# SCHEMATIC.net
KiCad netlist of a schematic drawn in EasyEDA
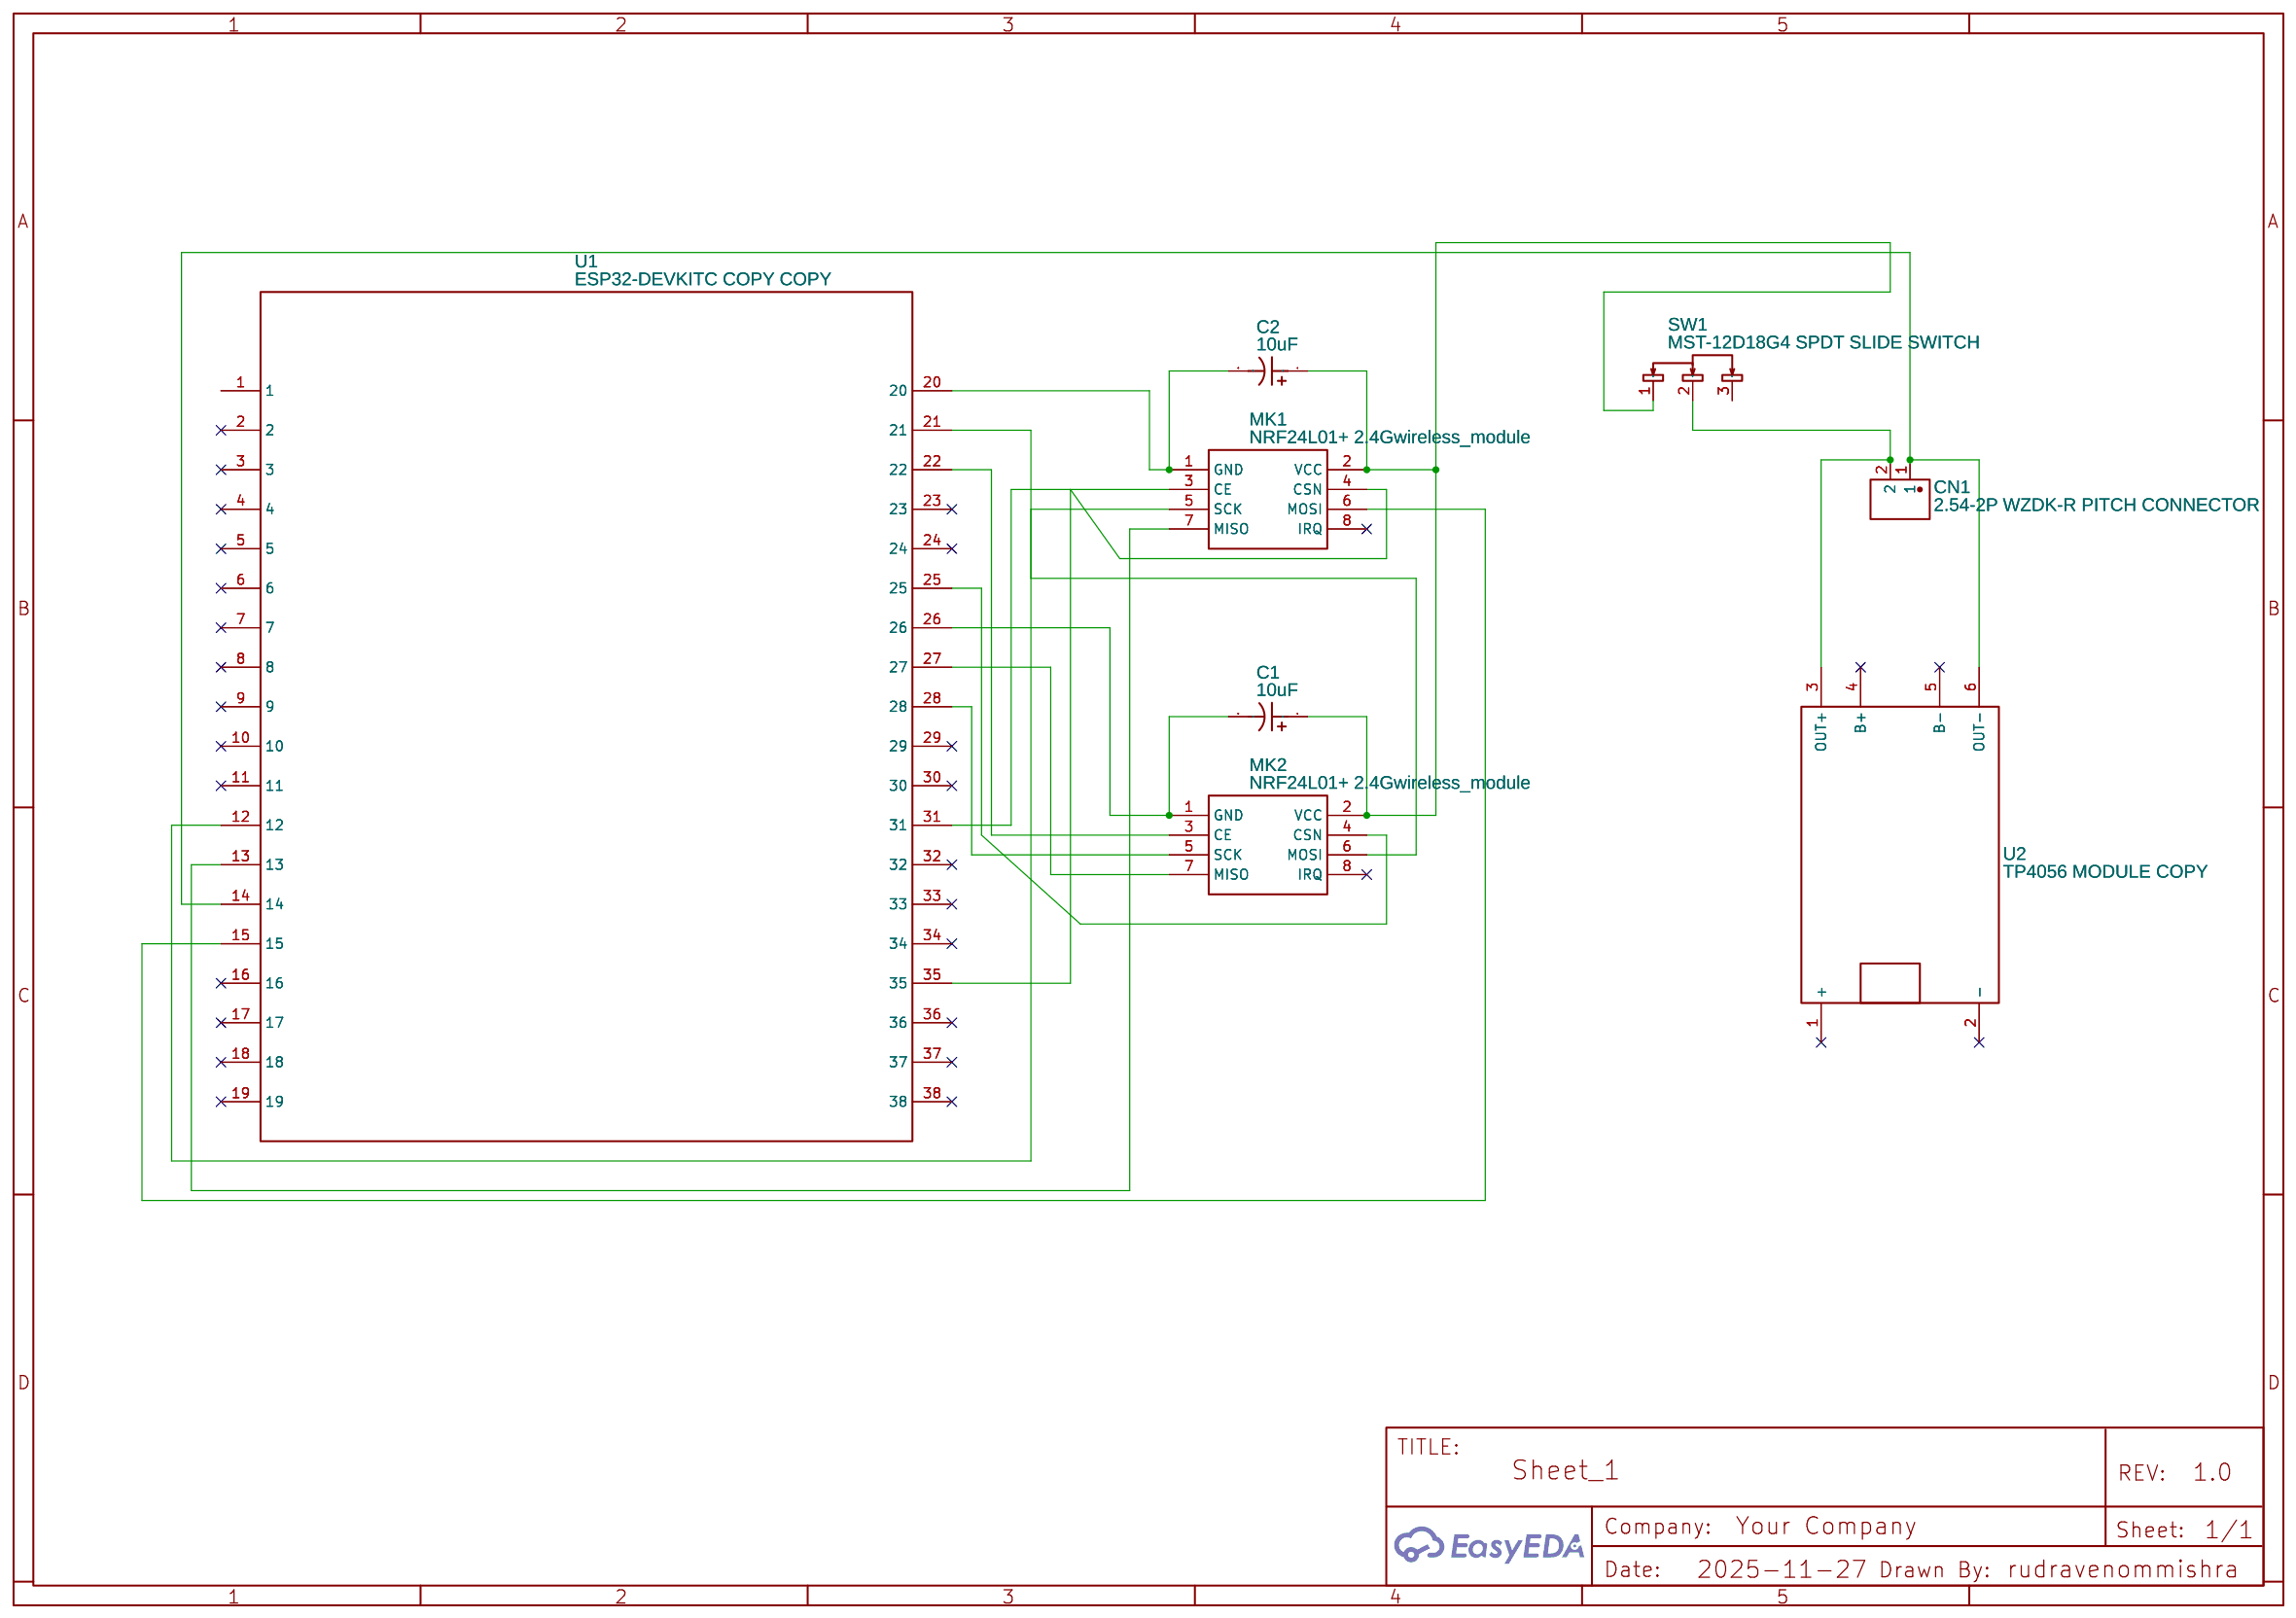
[diagram p0: schematic sheet]

(export (version "E")
  (design (tool "Eeschema 10.0.6"))
  (components
    (comp (ref "C1")
      (value "10uF")
      (fields (field (name "Manufacturer Part") "RYHG35V10UF5*8") (field (name "Manufacturer") "HONOR(荣誉)"))
      (libsource (lib "") (part "RYHG35V10UF5*8"))
    )
    (comp (ref "C2")
      (value "10uF")
      (fields (field (name "Manufacturer Part") "RYHG35V10UF5*8") (field (name "Manufacturer") "HONOR(荣誉)"))
      (libsource (lib "") (part "RYHG35V10UF5*8"))
    )
    (comp (ref "CN1")
      (value "2.54-2P WZDK-R PITCH CONNECTOR")
      (fields
        (field (name "Manufacturer Part") "2.54-2P WZDK-R Pitch Connector")
        (field (name "Manufacturer") "SHOU HAN(首韩)")
      )
      (libsource (lib "") (part "2.54-2P WZDK-R PITCH CONNECTOR"))
    )
    (comp (ref "MK1")
      (value "NRF24L01+ 2.4Gwireless_module")
      (fields
        (field (name "Manufacturer Part") "NRF24L01+功率加强版绑定2.4Gwireless module")
        (field (name "Manufacturer") "Ai-Thinker")
      )
      (libsource (lib "") (part "NRF24L01+ 2.4Gwireless_module"))
    )
    (comp (ref "MK2")
      (value "NRF24L01+ 2.4Gwireless_module")
      (fields
        (field (name "Manufacturer Part") "NRF24L01+功率加强版绑定2.4Gwireless module")
        (field (name "Manufacturer") "Ai-Thinker")
      )
      (libsource (lib "") (part "NRF24L01+ 2.4Gwireless_module"))
    )
    (comp (ref "SW1")
      (value "MST-12D18G4 SPDT SLIDE SWITCH")
      (fields
        (field (name "Manufacturer Part") "MST-12D18G4 SPDT Slide Switch")
        (field (name "Manufacturer") "SHOU HAN(首韩)")
      )
      (libsource (lib "") (part "MST-12D18G4 SPDT SLIDE SWITCH"))
    )
    (comp (ref "U1") (value "ESP32-DEVKITC COPY COPY") (libsource (lib "") (part "ESP32-DEVKITC COPY COPY")))
    (comp (ref "U2") (value "TP4056 MODULE COPY") (libsource (lib "") (part "TP4056 MODULE COPY")))
  )
  (nets
    (net (code "1") (name "Net-(MK1-CE)") (class "Default")
      (node (ref "MK1") (pin "3") (pinfunction "CE_3") (pintype "unspecified"))
      (node (ref "U1") (pin "31") (pinfunction "31_31") (pintype "unspecified"))
    )
    (net (code "2") (name "Net-(MK1-CSN)") (class "Default")
      (node (ref "MK1") (pin "4") (pinfunction "CSN_4") (pintype "unspecified"))
      (node (ref "U1") (pin "35") (pinfunction "35_35") (pintype "unspecified"))
    )
    (net (code "3") (name "Net-(MK1-GND)") (class "Default")
      (node (ref "C2") (pin "2") (pinfunction "2_2") (pintype "input"))
      (node (ref "MK1") (pin "1") (pinfunction "GND_1") (pintype "unspecified"))
      (node (ref "U1") (pin "20") (pinfunction "20_20") (pintype "unspecified"))
    )
    (net (code "4") (name "Net-(MK1-MISO)") (class "Default")
      (node (ref "MK1") (pin "7") (pinfunction "MISO_7") (pintype "unspecified"))
      (node (ref "U1") (pin "13") (pinfunction "13_13") (pintype "unspecified"))
    )
    (net (code "5") (name "Net-(MK1-MOSI)") (class "Default")
      (node (ref "MK1") (pin "6") (pinfunction "MOSI_6") (pintype "unspecified"))
      (node (ref "U1") (pin "15") (pinfunction "15_15") (pintype "unspecified"))
    )
    (net (code "6") (name "Net-(MK1-SCK)") (class "Default")
      (node (ref "MK1") (pin "5") (pinfunction "SCK_5") (pintype "unspecified"))
      (node (ref "U1") (pin "12") (pinfunction "12_12") (pintype "unspecified"))
    )
    (net (code "7") (name "Net-(MK1-VCC)") (class "Default")
      (node (ref "C1") (pin "1") (pinfunction "1_1") (pintype "input"))
      (node (ref "C2") (pin "1") (pinfunction "1_1") (pintype "input"))
      (node (ref "MK1") (pin "2") (pinfunction "VCC_2") (pintype "unspecified"))
      (node (ref "MK2") (pin "2") (pinfunction "VCC_2") (pintype "unspecified"))
      (node (ref "SW1") (pin "1") (pinfunction "1_1") (pintype "unspecified"))
    )
    (net (code "8") (name "Net-(MK2-CE)") (class "Default")
      (node (ref "MK2") (pin "3") (pinfunction "CE_3") (pintype "unspecified"))
      (node (ref "U1") (pin "22") (pinfunction "22_22") (pintype "unspecified"))
    )
    (net (code "9") (name "Net-(MK2-CSN)") (class "Default")
      (node (ref "MK2") (pin "4") (pinfunction "CSN_4") (pintype "unspecified"))
      (node (ref "U1") (pin "25") (pinfunction "25_25") (pintype "unspecified"))
    )
    (net (code "10") (name "Net-(MK2-GND)") (class "Default")
      (node (ref "C1") (pin "2") (pinfunction "2_2") (pintype "input"))
      (node (ref "MK2") (pin "1") (pinfunction "GND_1") (pintype "unspecified"))
      (node (ref "U1") (pin "26") (pinfunction "26_26") (pintype "unspecified"))
    )
    (net (code "11") (name "Net-(MK2-MISO)") (class "Default")
      (node (ref "MK2") (pin "7") (pinfunction "MISO_7") (pintype "unspecified"))
      (node (ref "U1") (pin "27") (pinfunction "27_27") (pintype "unspecified"))
    )
    (net (code "12") (name "Net-(MK2-MOSI)") (class "Default")
      (node (ref "MK2") (pin "6") (pinfunction "MOSI_6") (pintype "unspecified"))
      (node (ref "U1") (pin "21") (pinfunction "21_21") (pintype "unspecified"))
    )
    (net (code "13") (name "Net-(MK2-SCK)") (class "Default")
      (node (ref "MK2") (pin "5") (pinfunction "SCK_5") (pintype "unspecified"))
      (node (ref "U1") (pin "28") (pinfunction "28_28") (pintype "unspecified"))
    )
    (net (code "14") (name "Net-(U2-OUT+)") (class "Default")
      (node (ref "CN1") (pin "2") (pinfunction "2_2") (pintype "unspecified"))
      (node (ref "SW1") (pin "2") (pinfunction "2_2") (pintype "unspecified"))
      (node (ref "U2") (pin "3") (pinfunction "OUT+_3") (pintype "unspecified"))
    )
    (net (code "15") (name "Net-(U2-OUT-)") (class "Default")
      (node (ref "CN1") (pin "1") (pinfunction "1_1") (pintype "unspecified"))
      (node (ref "U1") (pin "14") (pinfunction "14_14") (pintype "unspecified"))
      (node (ref "U2") (pin "6") (pinfunction "OUT-_6") (pintype "unspecified"))
    )
    (net (code "16") (name "unconnected-(MK1-IRQ-Pad8)") (class "Default")
      (node (ref "MK1") (pin "8") (pinfunction "IRQ_8") (pintype "unspecified+no_connect"))
    )
    (net (code "17") (name "unconnected-(MK2-IRQ-Pad8)") (class "Default")
      (node (ref "MK2") (pin "8") (pinfunction "IRQ_8") (pintype "unspecified+no_connect"))
    )
    (net (code "18") (name "unconnected-(SW1-Pad3)") (class "Default")
      (node (ref "SW1") (pin "3") (pinfunction "3_3") (pintype "unspecified"))
    )
    (net (code "19") (name "unconnected-(U1-Pad1)") (class "Default")
      (node (ref "U1") (pin "1") (pinfunction "1_1") (pintype "unspecified"))
    )
    (net (code "20") (name "unconnected-(U1-Pad2)") (class "Default")
      (node (ref "U1") (pin "2") (pinfunction "2_2") (pintype "unspecified+no_connect"))
    )
    (net (code "21") (name "unconnected-(U1-Pad3)") (class "Default")
      (node (ref "U1") (pin "3") (pinfunction "3_3") (pintype "unspecified+no_connect"))
    )
    (net (code "22") (name "unconnected-(U1-Pad4)") (class "Default")
      (node (ref "U1") (pin "4") (pinfunction "4_4") (pintype "unspecified+no_connect"))
    )
    (net (code "23") (name "unconnected-(U1-Pad5)") (class "Default")
      (node (ref "U1") (pin "5") (pinfunction "5_5") (pintype "unspecified+no_connect"))
    )
    (net (code "24") (name "unconnected-(U1-Pad6)") (class "Default")
      (node (ref "U1") (pin "6") (pinfunction "6_6") (pintype "unspecified+no_connect"))
    )
    (net (code "25") (name "unconnected-(U1-Pad7)") (class "Default")
      (node (ref "U1") (pin "7") (pinfunction "7_7") (pintype "unspecified+no_connect"))
    )
    (net (code "26") (name "unconnected-(U1-Pad8)") (class "Default")
      (node (ref "U1") (pin "8") (pinfunction "8_8") (pintype "unspecified+no_connect"))
    )
    (net (code "27") (name "unconnected-(U1-Pad9)") (class "Default")
      (node (ref "U1") (pin "9") (pinfunction "9_9") (pintype "unspecified+no_connect"))
    )
    (net (code "28") (name "unconnected-(U1-Pad10)") (class "Default")
      (node (ref "U1") (pin "10") (pinfunction "10_10") (pintype "unspecified+no_connect"))
    )
    (net (code "29") (name "unconnected-(U1-Pad11)") (class "Default")
      (node (ref "U1") (pin "11") (pinfunction "11_11") (pintype "unspecified+no_connect"))
    )
    (net (code "30") (name "unconnected-(U1-Pad16)") (class "Default")
      (node (ref "U1") (pin "16") (pinfunction "16_16") (pintype "unspecified+no_connect"))
    )
    (net (code "31") (name "unconnected-(U1-Pad17)") (class "Default")
      (node (ref "U1") (pin "17") (pinfunction "17_17") (pintype "unspecified+no_connect"))
    )
    (net (code "32") (name "unconnected-(U1-Pad18)") (class "Default")
      (node (ref "U1") (pin "18") (pinfunction "18_18") (pintype "unspecified+no_connect"))
    )
    (net (code "33") (name "unconnected-(U1-Pad19)") (class "Default")
      (node (ref "U1") (pin "19") (pinfunction "19_19") (pintype "unspecified+no_connect"))
    )
    (net (code "34") (name "unconnected-(U1-Pad23)") (class "Default")
      (node (ref "U1") (pin "23") (pinfunction "23_23") (pintype "unspecified+no_connect"))
    )
    (net (code "35") (name "unconnected-(U1-Pad24)") (class "Default")
      (node (ref "U1") (pin "24") (pinfunction "24_24") (pintype "unspecified+no_connect"))
    )
    (net (code "36") (name "unconnected-(U1-Pad29)") (class "Default")
      (node (ref "U1") (pin "29") (pinfunction "29_29") (pintype "unspecified+no_connect"))
    )
    (net (code "37") (name "unconnected-(U1-Pad30)") (class "Default")
      (node (ref "U1") (pin "30") (pinfunction "30_30") (pintype "unspecified+no_connect"))
    )
    (net (code "38") (name "unconnected-(U1-Pad32)") (class "Default")
      (node (ref "U1") (pin "32") (pinfunction "32_32") (pintype "unspecified+no_connect"))
    )
    (net (code "39") (name "unconnected-(U1-Pad33)") (class "Default")
      (node (ref "U1") (pin "33") (pinfunction "33_33") (pintype "unspecified+no_connect"))
    )
    (net (code "40") (name "unconnected-(U1-Pad34)") (class "Default")
      (node (ref "U1") (pin "34") (pinfunction "34_34") (pintype "unspecified+no_connect"))
    )
    (net (code "41") (name "unconnected-(U1-Pad36)") (class "Default")
      (node (ref "U1") (pin "36") (pinfunction "36_36") (pintype "unspecified+no_connect"))
    )
    (net (code "42") (name "unconnected-(U1-Pad37)") (class "Default")
      (node (ref "U1") (pin "37") (pinfunction "37_37") (pintype "unspecified+no_connect"))
    )
    (net (code "43") (name "unconnected-(U1-Pad38)") (class "Default")
      (node (ref "U1") (pin "38") (pinfunction "38_38") (pintype "unspecified+no_connect"))
    )
    (net (code "44") (name "unconnected-(U2-+-Pad1)") (class "Default")
      (node (ref "U2") (pin "1") (pinfunction "+_1") (pintype "unspecified+no_connect"))
    )
    (net (code "45") (name "unconnected-(U2---Pad2)") (class "Default")
      (node (ref "U2") (pin "2") (pinfunction "-_2") (pintype "unspecified+no_connect"))
    )
    (net (code "46") (name "unconnected-(U2-B+-Pad4)") (class "Default")
      (node (ref "U2") (pin "4") (pinfunction "B+_4") (pintype "unspecified+no_connect"))
    )
    (net (code "47") (name "unconnected-(U2-B--Pad5)") (class "Default")
      (node (ref "U2") (pin "5") (pinfunction "B-_5") (pintype "unspecified+no_connect"))
    )
  )
)
